# 10_MountingHoles.net
KiCad netlist of a schematic drawn in Altium Designer
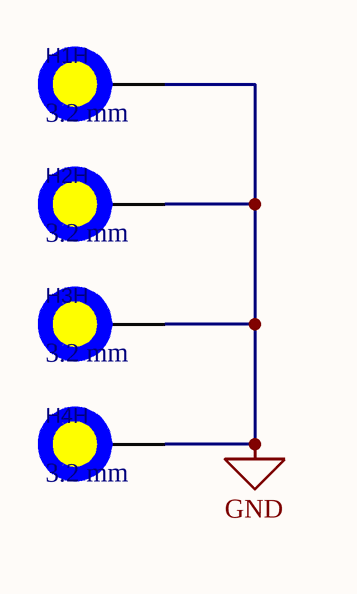
[diagram p0: 10_MountingHoles.SchDoc]

(export (version "E")
  (design (tool "Eeschema 10.0.6"))
  (components
    (comp (ref "H1H")
      (value "3.2 mm")
      (footprint "MountingHole_3.2mm_M3_Pad_Via_Mask")
      (libsource (lib "Lib_MountingHole") (part "MountingHole_Pad_3.2mm"))
    )
    (comp (ref "H2H")
      (value "3.2 mm")
      (footprint "MountingHole_3.2mm_M3_Pad_Via_Mask")
      (libsource (lib "Lib_MountingHole") (part "MountingHole_Pad_3.2mm"))
    )
    (comp (ref "H3H")
      (value "3.2 mm")
      (footprint "MountingHole_3.2mm_M3_Pad_Via_Mask")
      (libsource (lib "Lib_MountingHole") (part "MountingHole_Pad_3.2mm"))
    )
    (comp (ref "H4H")
      (value "3.2 mm")
      (footprint "MountingHole_3.2mm_M3_Pad_Via_Mask")
      (libsource (lib "Lib_MountingHole") (part "MountingHole_Pad_3.2mm"))
    )
  )
  (nets
    (net (code "1") (name "GND") (class "Default")
      (node (ref "H1H") (pin "1") (pinfunction "1_1") (pintype "passive"))
      (node (ref "H2H") (pin "1") (pinfunction "1_1") (pintype "passive"))
      (node (ref "H3H") (pin "1") (pinfunction "1_1") (pintype "passive"))
      (node (ref "H4H") (pin "1") (pinfunction "1_1") (pintype "passive"))
    )
  )
)
